# barometer_copy.net
KiCad netlist of a schematic drawn in EAGLE
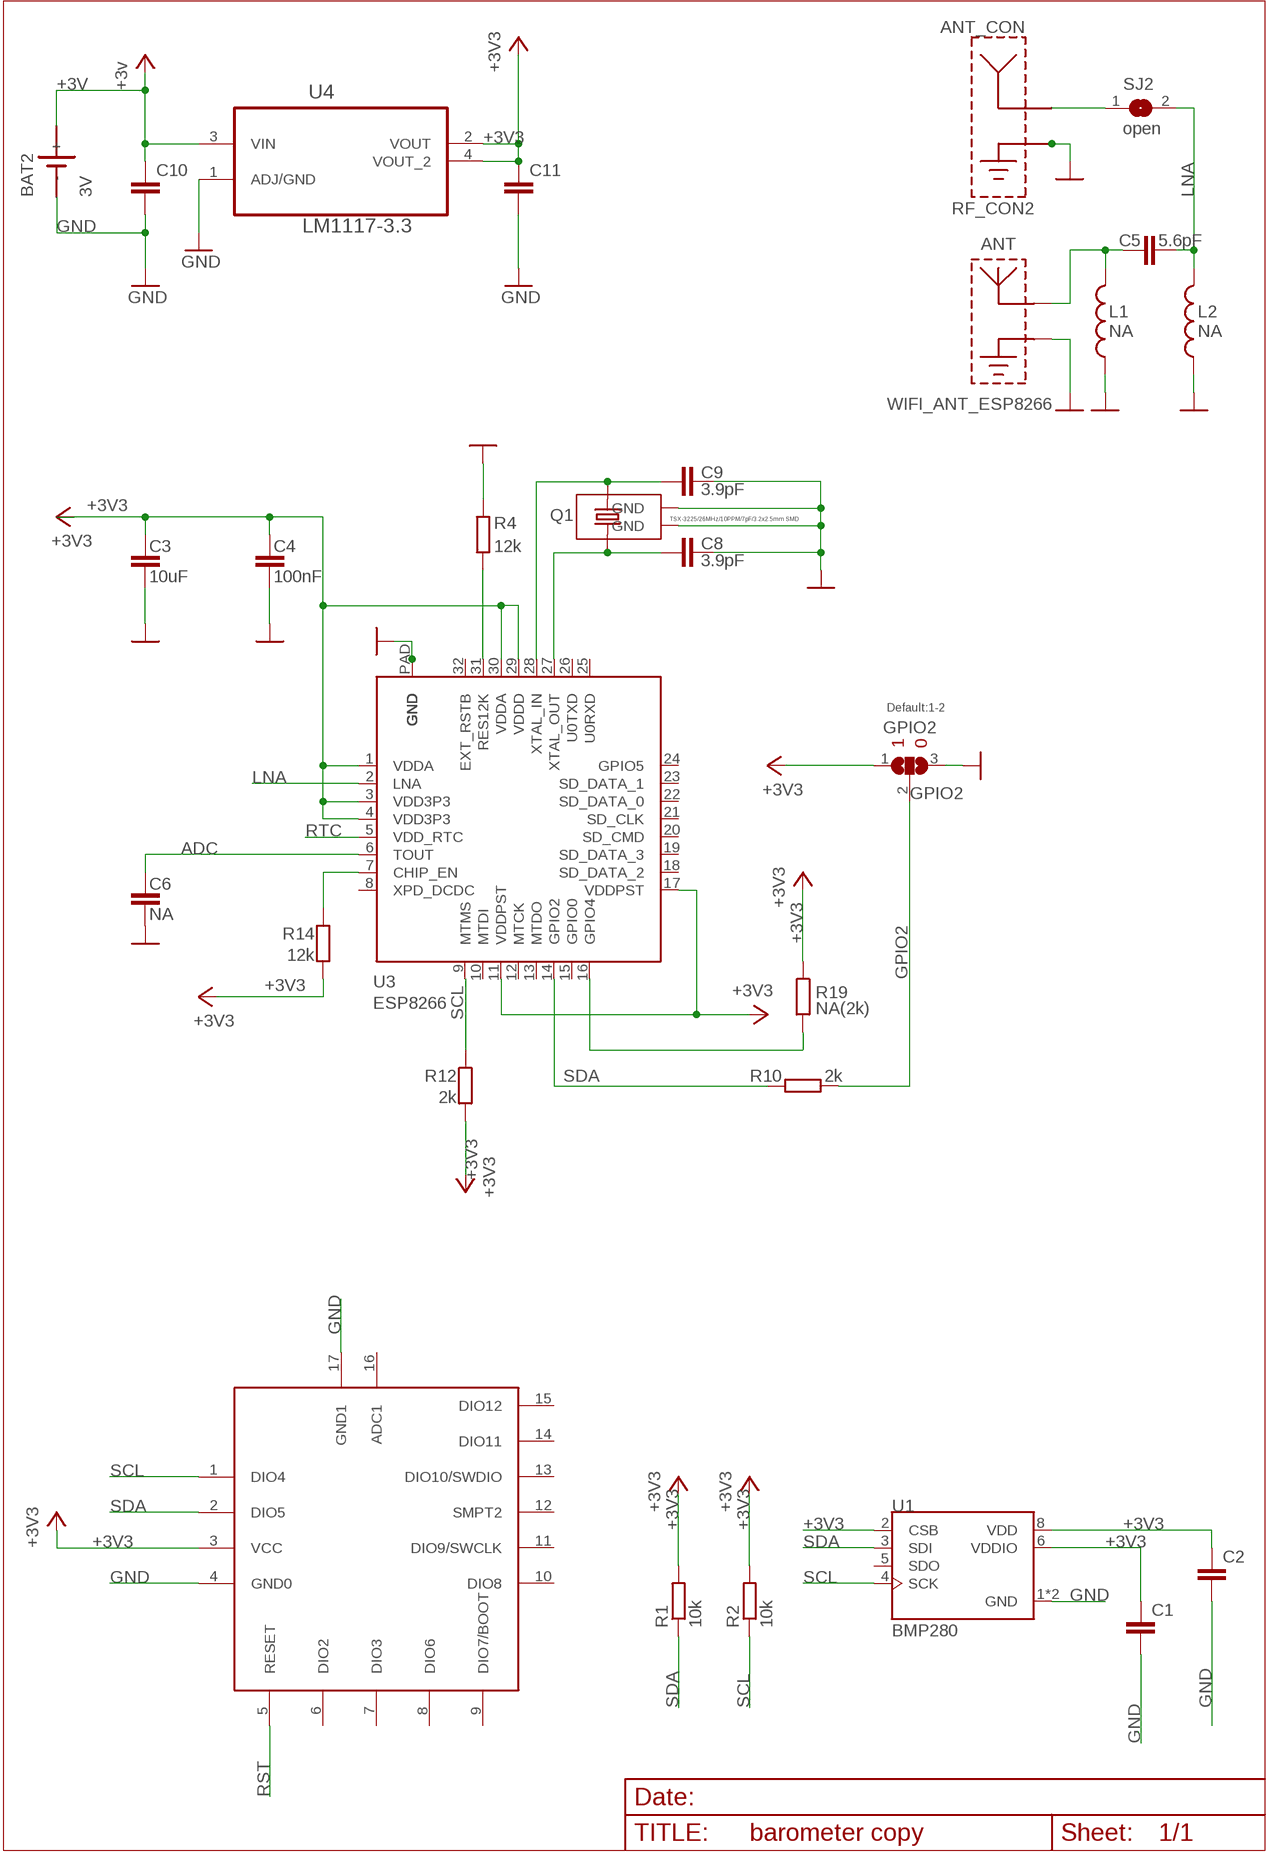
[diagram p0: schematic, sheet 1, part 1 of 2]
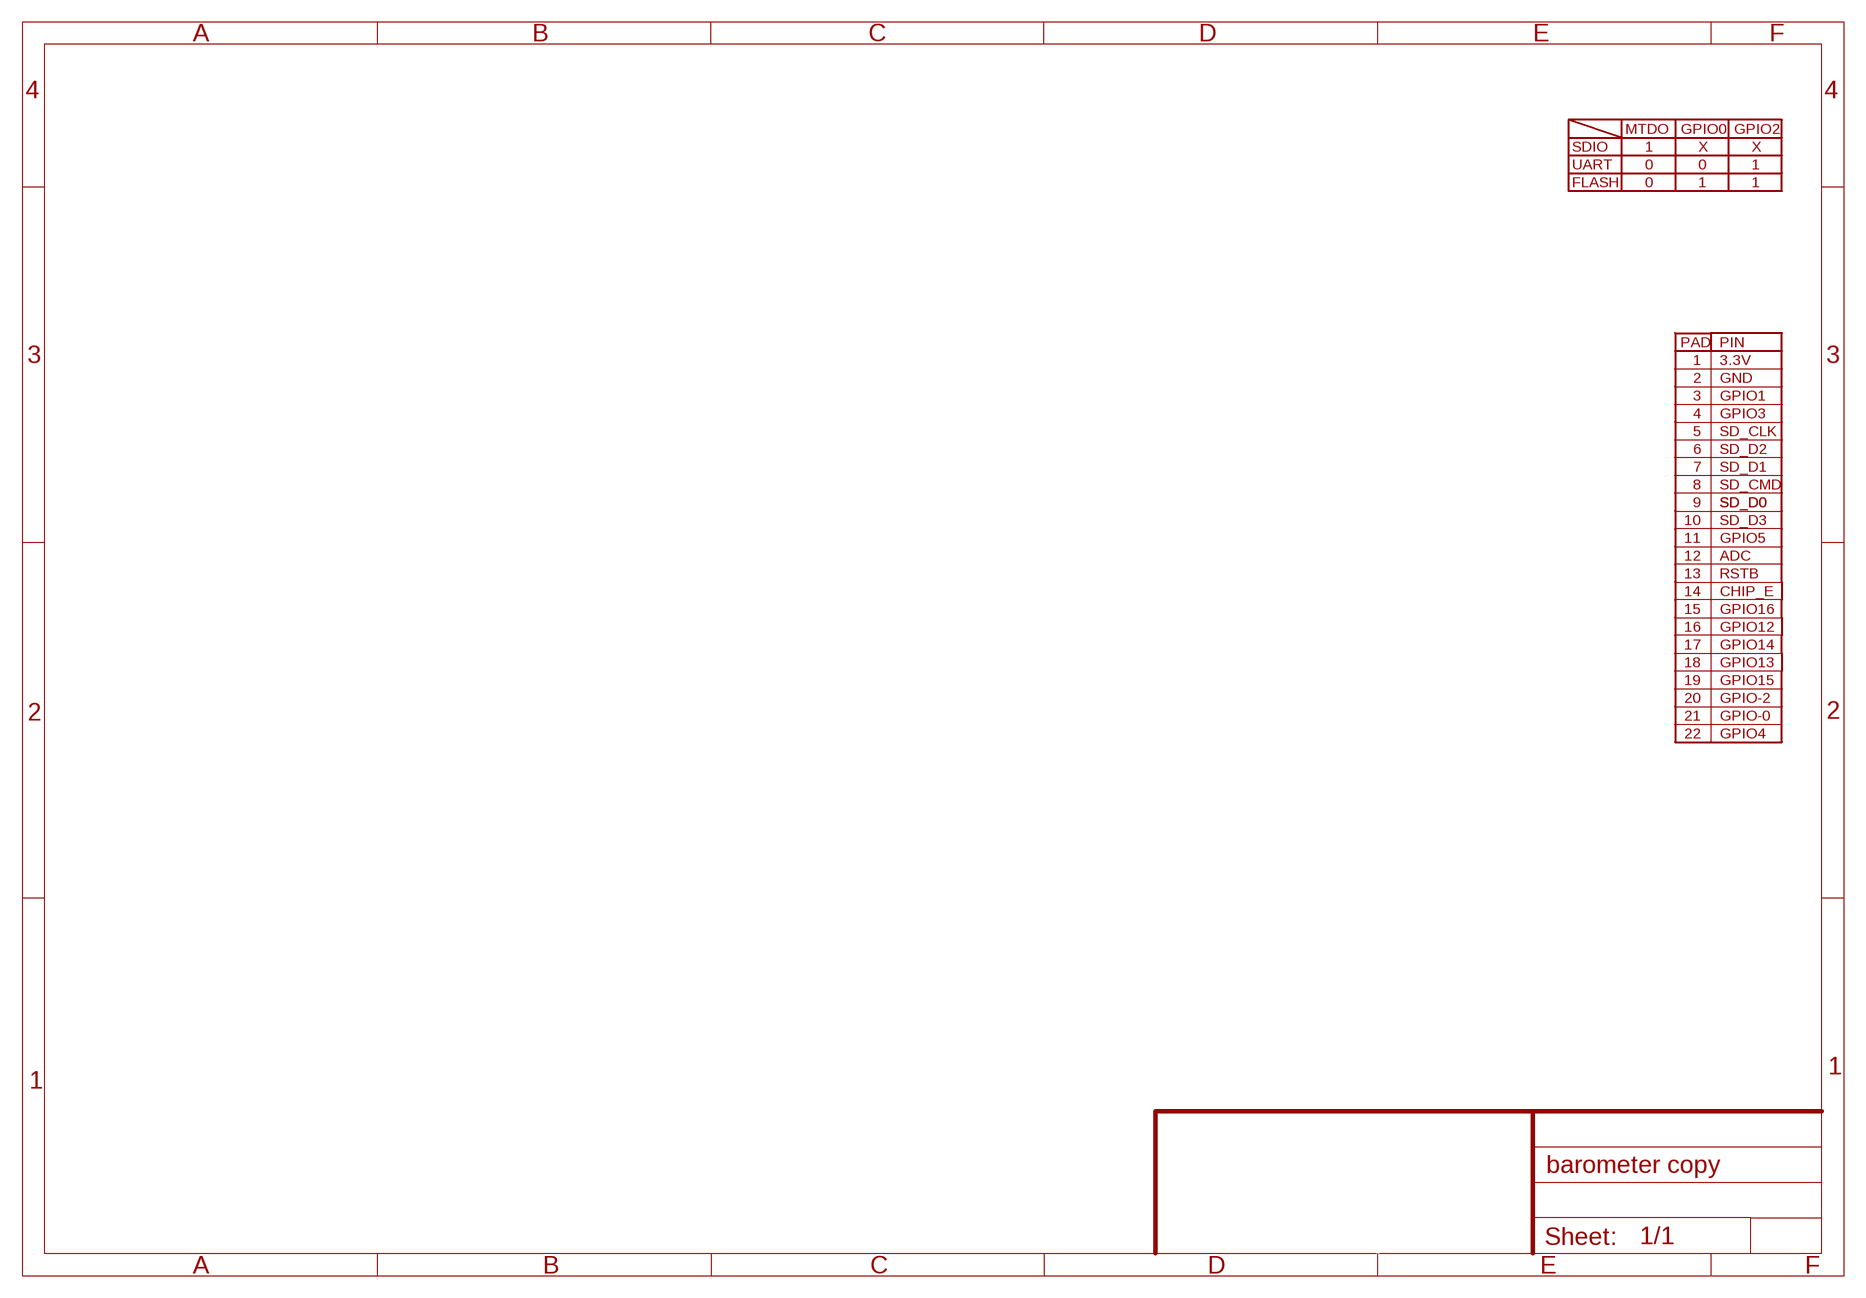
[diagram p1: schematic, sheet 1, part 2 of 2]

(export (version "E")
  (design (tool "Eeschema 10.0.6"))
  (components
    (comp (ref "ANT")
      (value "WIFI_ANT_ESP8266")
      (footprint "eagle-import:ESP8266_ANT")
      (libsource (lib "eagle-import") (part "WIFI_ANT_ESP8266"))
    )
    (comp (ref "ANT_CON")
      (value "RF_CON2")
      (footprint "eagle-import:RF_CONNECTOR_I-PEX_NO_CREAM")
      (libsource (lib "eagle-import") (part "RF_CON2"))
    )
    (comp (ref "BAT2")
      (value "3V")
      (footprint "eagle-import:SN2032")
      (libsource (lib "eagle-import") (part "SN2032"))
    )
    (comp (ref "C1")
      (value "47u")
      (footprint "eagle-import:C1206")
      (libsource (lib "eagle-import") (part "rcl_334_C-EUC1206"))
    )
    (comp (ref "C2")
      (value "47u")
      (footprint "eagle-import:C1206")
      (libsource (lib "eagle-import") (part "rcl_334_C-EUC1206"))
    )
    (comp (ref "C3")
      (value "10uF")
      (footprint "eagle-import:C0603_DWS")
      (libsource (lib "eagle-import") (part "C-EUC0603_DWS"))
    )
    (comp (ref "C4")
      (value "100nF")
      (footprint "eagle-import:C0402_TI")
      (libsource (lib "eagle-import") (part "C-EUC0402_TI"))
    )
    (comp (ref "C5")
      (value "5.6pF")
      (footprint "eagle-import:C0402_TI")
      (libsource (lib "eagle-import") (part "C-EUC0402_TI"))
    )
    (comp (ref "C6")
      (value "NA")
      (footprint "eagle-import:C0402_TI")
      (libsource (lib "eagle-import") (part "C-EUC0402_TI"))
    )
    (comp (ref "C8")
      (value "3.9pF")
      (footprint "eagle-import:C0402_TI")
      (libsource (lib "eagle-import") (part "C-EUC0402_TI"))
    )
    (comp (ref "C9")
      (value "3.9pF")
      (footprint "eagle-import:C0402_TI")
      (libsource (lib "eagle-import") (part "C-EUC0402_TI"))
    )
    (comp (ref "C10")
      (value "47u")
      (footprint "eagle-import:C1206")
      (libsource (lib "eagle-import") (part "rcl_334_C-EUC1206"))
    )
    (comp (ref "C11")
      (value "10u")
      (footprint "eagle-import:C1206")
      (libsource (lib "eagle-import") (part "rcl_334_C-EUC1206"))
    )
    (comp (ref "GPIO2")
      (value "Default:1-2")
      (footprint "eagle-import:SJ_2_SMALLER")
      (libsource (lib "eagle-import") (part "SJ2W4"))
    )
    (comp (ref "L1")
      (value "NA")
      (footprint "eagle-import:L0402_TI")
      (libsource (lib "eagle-import") (part "L-USL0402_TI"))
    )
    (comp (ref "L2")
      (value "NA")
      (footprint "eagle-import:L0402_TI")
      (libsource (lib "eagle-import") (part "L-USL0402_TI"))
    )
    (comp (ref "Q1")
      (value "TSX-3225/26MHz/10PPM/7pF/3.2x2.5mm SMD")
      (footprint "eagle-import:NX3225SA")
      (libsource (lib "eagle-import") (part "SMALL_SMD_CRYSTAL_1"))
    )
    (comp (ref "R1")
      (value "10k")
      (footprint "eagle-import:R0402")
      (libsource (lib "eagle-import") (part "rcl_334_R-EU_R0402"))
    )
    (comp (ref "R2")
      (value "10k")
      (footprint "eagle-import:R0402")
      (libsource (lib "eagle-import") (part "rcl_334_R-EU_R0402"))
    )
    (comp (ref "R4")
      (value "12k")
      (footprint "eagle-import:R0402_TI")
      (libsource (lib "eagle-import") (part "R-EU_R0402_TI"))
    )
    (comp (ref "R10")
      (value "2k")
      (footprint "eagle-import:R0402_TI")
      (libsource (lib "eagle-import") (part "R-EU_R0402_TI"))
    )
    (comp (ref "R12")
      (value "2k")
      (footprint "eagle-import:R0402_TI")
      (libsource (lib "eagle-import") (part "R-EU_R0402_TI"))
    )
    (comp (ref "R14")
      (value "12k")
      (footprint "eagle-import:R0402_TI")
      (libsource (lib "eagle-import") (part "R-EU_R0402_TI"))
    )
    (comp (ref "R19")
      (value "NA(2k)")
      (footprint "eagle-import:R0402_TI")
      (libsource (lib "eagle-import") (part "R-EU_R0402_TI"))
    )
    (comp (ref "SJ2")
      (value "open")
      (footprint "eagle-import:SJ_1_SMALLER")
      (libsource (lib "eagle-import") (part "SJSJ_SMALLER"))
    )
    (comp (ref "U$1")
      (value "BLUENRG-234BLEMODULE")
      (footprint "eagle-import:BLUENRG-234BLEMODULE")
      (libsource (lib "eagle-import") (part "BLUENRG-234BLEMODULE"))
    )
    (comp (ref "U1")
      (value "BMP280")
      (footprint "eagle-import:XDCR_BMP280")
      (fields (field (name "MF") "Bosch"))
      (libsource (lib "eagle-import") (part "BMP280"))
    )
    (comp (ref "U3")
      (value "ESP8266")
      (footprint "eagle-import:QFN32_PAD")
      (libsource (lib "eagle-import") (part "ESP8266"))
    )
    (comp (ref "U4")
      (value "LM1117-3.3")
      (footprint "eagle-import:SOT230")
      (fields (field (name "MF") "Texas Instruments"))
      (libsource (lib "eagle-import") (part "LM1117-3.3"))
    )
  )
  (nets
    (net (code "1") (name "+3V3") (class "Default")
      (node (ref "C1") (pin "1") (pinfunction "1_1") (pintype "passive"))
      (node (ref "C11") (pin "1") (pinfunction "1_1") (pintype "passive"))
      (node (ref "C2") (pin "1") (pinfunction "1_1") (pintype "passive"))
      (node (ref "C3") (pin "1") (pinfunction "1_1") (pintype "passive"))
      (node (ref "C4") (pin "1") (pinfunction "1_1") (pintype "passive"))
      (node (ref "GPIO2") (pin "1") (pinfunction "1_1") (pintype "passive"))
      (node (ref "R1") (pin "2") (pinfunction "2_2") (pintype "passive"))
      (node (ref "R12") (pin "2") (pinfunction "2_2") (pintype "passive"))
      (node (ref "R14") (pin "2") (pinfunction "2_2") (pintype "passive"))
      (node (ref "R19") (pin "1") (pinfunction "1_1") (pintype "passive"))
      (node (ref "R2") (pin "2") (pinfunction "2_2") (pintype "passive"))
      (node (ref "U$1") (pin "3") (pinfunction "VCC_3") (pintype "bidirectional"))
      (node (ref "U1") (pin "2") (pinfunction "CSB_2") (pintype "input"))
      (node (ref "U1") (pin "6") (pinfunction "VDDIO_6") (pintype "power_in"))
      (node (ref "U1") (pin "8") (pinfunction "VDD_8") (pintype "power_in"))
      (node (ref "U3") (pin "1") (pinfunction "VDDA_1") (pintype "bidirectional"))
      (node (ref "U3") (pin "11") (pinfunction "VDDPST_11") (pintype "bidirectional"))
      (node (ref "U3") (pin "17") (pinfunction "VDDPST_17") (pintype "bidirectional"))
      (node (ref "U3") (pin "29") (pinfunction "VDDD_29") (pintype "bidirectional"))
      (node (ref "U3") (pin "3") (pinfunction "VDD3P3_3") (pintype "bidirectional"))
      (node (ref "U3") (pin "30") (pinfunction "VDDA_30") (pintype "bidirectional"))
      (node (ref "U3") (pin "4") (pinfunction "VDD3P3_4") (pintype "bidirectional"))
      (node (ref "U4") (pin "2") (pinfunction "VOUT_2") (pintype "output"))
      (node (ref "U4") (pin "4") (pinfunction "VOUT_2_4") (pintype "output"))
    )
    (net (code "2") (name "+3v") (class "Default")
      (node (ref "BAT2") (pin "+") (pinfunction "+_+") (pintype "passive"))
      (node (ref "C10") (pin "1") (pinfunction "1_1") (pintype "passive"))
      (node (ref "U4") (pin "3") (pinfunction "VIN_3") (pintype "input"))
    )
    (net (code "3") (name "/ADC") (class "Default")
      (node (ref "C6") (pin "1") (pinfunction "1_1") (pintype "passive"))
      (node (ref "U3") (pin "6") (pinfunction "TOUT_6") (pintype "bidirectional"))
    )
    (net (code "4") (name "/GPIO2") (class "Default")
      (node (ref "GPIO2") (pin "2") (pinfunction "2_2") (pintype "passive"))
      (node (ref "R10") (pin "1") (pinfunction "1_1") (pintype "passive"))
    )
    (net (code "5") (name "/LNA") (class "Default")
      (node (ref "C5") (pin "2") (pinfunction "2_2") (pintype "passive"))
      (node (ref "L2") (pin "2") (pinfunction "2_2") (pintype "passive"))
      (node (ref "SJ2") (pin "2") (pinfunction "2_2") (pintype "passive"))
      (node (ref "U3") (pin "2") (pinfunction "LNA_2") (pintype "bidirectional"))
    )
    (net (code "6") (name "/RST") (class "Default")
      (node (ref "U$1") (pin "5") (pinfunction "RESET_5") (pintype "bidirectional"))
    )
    (net (code "7") (name "/RTC") (class "Default")
      (node (ref "U3") (pin "5") (pinfunction "VDD_RTC_5") (pintype "bidirectional"))
    )
    (net (code "8") (name "/SCL") (class "Default")
      (node (ref "R12") (pin "1") (pinfunction "1_1") (pintype "passive"))
      (node (ref "R2") (pin "1") (pinfunction "1_1") (pintype "passive"))
      (node (ref "U$1") (pin "1") (pinfunction "DIO4_1") (pintype "bidirectional"))
      (node (ref "U1") (pin "4") (pinfunction "SCK_4") (pintype "input"))
      (node (ref "U3") (pin "9") (pinfunction "MTMS_9") (pintype "bidirectional"))
    )
    (net (code "9") (name "/SDA") (class "Default")
      (node (ref "R1") (pin "1") (pinfunction "1_1") (pintype "passive"))
      (node (ref "R10") (pin "2") (pinfunction "2_2") (pintype "passive"))
      (node (ref "U$1") (pin "2") (pinfunction "DIO5_2") (pintype "bidirectional"))
      (node (ref "U1") (pin "3") (pinfunction "SDI_3") (pintype "bidirectional"))
      (node (ref "U3") (pin "14") (pinfunction "GPIO2_14") (pintype "bidirectional"))
    )
    (net (code "10") (name "GND") (class "Default")
      (node (ref "ANT") (pin "GND") (pinfunction "GND_GND") (pintype "input"))
      (node (ref "ANT_CON") (pin "1") (pinfunction "GND_1_1") (pintype "input"))
      (node (ref "ANT_CON") (pin "2") (pinfunction "GND_2_2") (pintype "input"))
      (node (ref "BAT2") (pin "-") (pinfunction "-_-") (pintype "passive"))
      (node (ref "C1") (pin "2") (pinfunction "2_2") (pintype "passive"))
      (node (ref "C10") (pin "2") (pinfunction "2_2") (pintype "passive"))
      (node (ref "C11") (pin "2") (pinfunction "2_2") (pintype "passive"))
      (node (ref "C2") (pin "2") (pinfunction "2_2") (pintype "passive"))
      (node (ref "C3") (pin "2") (pinfunction "2_2") (pintype "passive"))
      (node (ref "C4") (pin "2") (pinfunction "2_2") (pintype "passive"))
      (node (ref "C6") (pin "2") (pinfunction "2_2") (pintype "passive"))
      (node (ref "C8") (pin "1") (pinfunction "1_1") (pintype "passive"))
      (node (ref "C9") (pin "1") (pinfunction "1_1") (pintype "passive"))
      (node (ref "GPIO2") (pin "3") (pinfunction "3_3") (pintype "passive"))
      (node (ref "L1") (pin "1") (pinfunction "1_1") (pintype "passive"))
      (node (ref "L2") (pin "1") (pinfunction "1_1") (pintype "passive"))
      (node (ref "Q1") (pin "NC_1") (pinfunction "GND_NC_1") (pintype "power_in"))
      (node (ref "Q1") (pin "NC_2") (pinfunction "GND_NC_2") (pintype "power_in"))
      (node (ref "R4") (pin "2") (pinfunction "2_2") (pintype "passive"))
      (node (ref "U$1") (pin "17") (pinfunction "GND1_17") (pintype "bidirectional"))
      (node (ref "U$1") (pin "4") (pinfunction "GND0_4") (pintype "bidirectional"))
      (node (ref "U1") (pin "1") (pinfunction "GND_1") (pintype "power_in"))
      (node (ref "U1") (pin "7") (pinfunction "GND_7") (pintype "power_in"))
      (node (ref "U3") (pin "P$1") (pinfunction "GND_P$1") (pintype "bidirectional"))
      (node (ref "U3") (pin "P$2") (pinfunction "GND_P$2") (pintype "bidirectional"))
      (node (ref "U3") (pin "P$3") (pinfunction "GND_P$3") (pintype "bidirectional"))
      (node (ref "U3") (pin "P$4") (pinfunction "GND_P$4") (pintype "bidirectional"))
      (node (ref "U3") (pin "P$5") (pinfunction "GND_P$5") (pintype "bidirectional"))
      (node (ref "U3") (pin "P$6") (pinfunction "GND_P$6") (pintype "bidirectional"))
      (node (ref "U3") (pin "P$7") (pinfunction "GND_P$7") (pintype "bidirectional"))
      (node (ref "U3") (pin "P$8") (pinfunction "GND_P$8") (pintype "bidirectional"))
      (node (ref "U3") (pin "P$9") (pinfunction "GND_P$9") (pintype "bidirectional"))
      (node (ref "U3") (pin "PAD") (pinfunction "GND_PAD") (pintype "bidirectional"))
      (node (ref "U4") (pin "1") (pinfunction "ADJ/GND_1") (pintype "passive"))
    )
    (net (code "11") (name "Net-(ANT-PadANT)") (class "Default")
      (node (ref "ANT") (pin "ANT") (pinfunction "ANT_ANT") (pintype "input"))
      (node (ref "C5") (pin "1") (pinfunction "1_1") (pintype "passive"))
      (node (ref "L1") (pin "2") (pinfunction "2_2") (pintype "passive"))
    )
    (net (code "12") (name "Net-(ANT_CON-PadANT)") (class "Default")
      (node (ref "ANT_CON") (pin "ANT") (pinfunction "ANT_ANT") (pintype "power_in"))
      (node (ref "SJ2") (pin "1") (pinfunction "1_1") (pintype "passive"))
    )
    (net (code "13") (name "Net-(U3-CHIP_EN)") (class "Default")
      (node (ref "R14") (pin "1") (pinfunction "1_1") (pintype "passive"))
      (node (ref "U3") (pin "7") (pinfunction "CHIP_EN_7") (pintype "bidirectional"))
    )
    (net (code "14") (name "Net-(U3-GPIO4)") (class "Default")
      (node (ref "R19") (pin "2") (pinfunction "2_2") (pintype "passive"))
      (node (ref "U3") (pin "16") (pinfunction "GPIO4_16") (pintype "bidirectional"))
    )
    (net (code "15") (name "Net-(U3-RES12K)") (class "Default")
      (node (ref "R4") (pin "1") (pinfunction "1_1") (pintype "passive"))
      (node (ref "U3") (pin "31") (pinfunction "RES12K_31") (pintype "bidirectional"))
    )
    (net (code "16") (name "Net-(U3-XTAL_IN)") (class "Default")
      (node (ref "C9") (pin "2") (pinfunction "2_2") (pintype "passive"))
      (node (ref "Q1") (pin "1") (pinfunction "1_1") (pintype "input"))
      (node (ref "U3") (pin "28") (pinfunction "XTAL_IN_28") (pintype "bidirectional"))
    )
    (net (code "17") (name "Net-(U3-XTAL_OUT)") (class "Default")
      (node (ref "C8") (pin "2") (pinfunction "2_2") (pintype "passive"))
      (node (ref "Q1") (pin "2") (pinfunction "2_2") (pintype "input"))
      (node (ref "U3") (pin "27") (pinfunction "XTAL_OUT_27") (pintype "bidirectional"))
    )
    (net (code "18") (name "unconnected-(U$1-ADC1-Pad16)") (class "Default")
      (node (ref "U$1") (pin "16") (pinfunction "ADC1_16") (pintype "bidirectional"))
    )
    (net (code "19") (name "unconnected-(U$1-DIO2-Pad6)") (class "Default")
      (node (ref "U$1") (pin "6") (pinfunction "DIO2_6") (pintype "bidirectional"))
    )
    (net (code "20") (name "unconnected-(U$1-DIO3-Pad7)") (class "Default")
      (node (ref "U$1") (pin "7") (pinfunction "DIO3_7") (pintype "bidirectional"))
    )
    (net (code "21") (name "unconnected-(U$1-DIO6-Pad8)") (class "Default")
      (node (ref "U$1") (pin "8") (pinfunction "DIO6_8") (pintype "bidirectional"))
    )
    (net (code "22") (name "unconnected-(U$1-DIO7{slash}BOOT-Pad9)") (class "Default")
      (node (ref "U$1") (pin "9") (pinfunction "DIO7/BOOT_9") (pintype "bidirectional"))
    )
    (net (code "23") (name "unconnected-(U$1-DIO8-Pad10)") (class "Default")
      (node (ref "U$1") (pin "10") (pinfunction "DIO8_10") (pintype "bidirectional"))
    )
    (net (code "24") (name "unconnected-(U$1-DIO9{slash}SWCLK-Pad11)") (class "Default")
      (node (ref "U$1") (pin "11") (pinfunction "DIO9/SWCLK_11") (pintype "bidirectional"))
    )
    (net (code "25") (name "unconnected-(U$1-DIO10{slash}SWDIO-Pad13)") (class "Default")
      (node (ref "U$1") (pin "13") (pinfunction "DIO10/SWDIO_13") (pintype "bidirectional"))
    )
    (net (code "26") (name "unconnected-(U$1-DIO11-Pad14)") (class "Default")
      (node (ref "U$1") (pin "14") (pinfunction "DIO11_14") (pintype "bidirectional"))
    )
    (net (code "27") (name "unconnected-(U$1-DIO12-Pad15)") (class "Default")
      (node (ref "U$1") (pin "15") (pinfunction "DIO12_15") (pintype "bidirectional"))
    )
    (net (code "28") (name "unconnected-(U$1-SMPT2-Pad12)") (class "Default")
      (node (ref "U$1") (pin "12") (pinfunction "SMPT2_12") (pintype "bidirectional"))
    )
    (net (code "29") (name "unconnected-(U1-SDO-Pad5)") (class "Default")
      (node (ref "U1") (pin "5") (pinfunction "SDO_5") (pintype "bidirectional"))
    )
    (net (code "30") (name "unconnected-(U3-EXT_RSTB-Pad32)") (class "Default")
      (node (ref "U3") (pin "32") (pinfunction "EXT_RSTB_32") (pintype "bidirectional"))
    )
    (net (code "31") (name "unconnected-(U3-GPIO0-Pad15)") (class "Default")
      (node (ref "U3") (pin "15") (pinfunction "GPIO0_15") (pintype "bidirectional"))
    )
    (net (code "32") (name "unconnected-(U3-GPIO5-Pad24)") (class "Default")
      (node (ref "U3") (pin "24") (pinfunction "GPIO5_24") (pintype "bidirectional"))
    )
    (net (code "33") (name "unconnected-(U3-MTCK-Pad12)") (class "Default")
      (node (ref "U3") (pin "12") (pinfunction "MTCK_12") (pintype "bidirectional"))
    )
    (net (code "34") (name "unconnected-(U3-MTDI-Pad10)") (class "Default")
      (node (ref "U3") (pin "10") (pinfunction "MTDI_10") (pintype "bidirectional"))
    )
    (net (code "35") (name "unconnected-(U3-MTDO-Pad13)") (class "Default")
      (node (ref "U3") (pin "13") (pinfunction "MTDO_13") (pintype "bidirectional"))
    )
    (net (code "36") (name "unconnected-(U3-SD_CLK-Pad21)") (class "Default")
      (node (ref "U3") (pin "21") (pinfunction "SD_CLK_21") (pintype "bidirectional"))
    )
    (net (code "37") (name "unconnected-(U3-SD_CMD-Pad20)") (class "Default")
      (node (ref "U3") (pin "20") (pinfunction "SD_CMD_20") (pintype "bidirectional"))
    )
    (net (code "38") (name "unconnected-(U3-SD_DATA_0-Pad22)") (class "Default")
      (node (ref "U3") (pin "22") (pinfunction "SD_DATA_0_22") (pintype "bidirectional"))
    )
    (net (code "39") (name "unconnected-(U3-SD_DATA_1-Pad23)") (class "Default")
      (node (ref "U3") (pin "23") (pinfunction "SD_DATA_1_23") (pintype "bidirectional"))
    )
    (net (code "40") (name "unconnected-(U3-SD_DATA_2-Pad18)") (class "Default")
      (node (ref "U3") (pin "18") (pinfunction "SD_DATA_2_18") (pintype "bidirectional"))
    )
    (net (code "41") (name "unconnected-(U3-SD_DATA_3-Pad19)") (class "Default")
      (node (ref "U3") (pin "19") (pinfunction "SD_DATA_3_19") (pintype "bidirectional"))
    )
    (net (code "42") (name "unconnected-(U3-U0RXD-Pad25)") (class "Default")
      (node (ref "U3") (pin "25") (pinfunction "U0RXD_25") (pintype "bidirectional"))
    )
    (net (code "43") (name "unconnected-(U3-U0TXD-Pad26)") (class "Default")
      (node (ref "U3") (pin "26") (pinfunction "U0TXD_26") (pintype "bidirectional"))
    )
    (net (code "44") (name "unconnected-(U3-XPD_DCDC-Pad8)") (class "Default")
      (node (ref "U3") (pin "8") (pinfunction "XPD_DCDC_8") (pintype "bidirectional"))
    )
  )
)
